# Adafruit_PowerBoost_1000_Basic.net
KiCad netlist of a schematic drawn in EAGLE
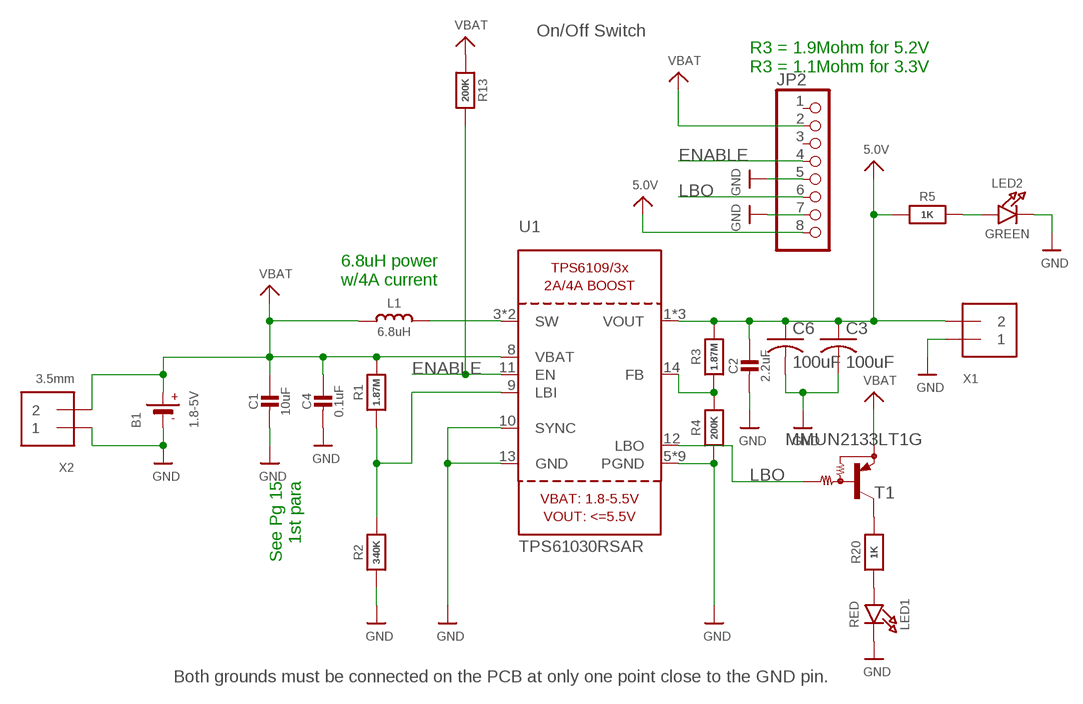
[diagram p0: schematic, sheet 1]

(export (version "E")
  (design (tool "Eeschema 10.0.6"))
  (components
    (comp (ref "B1")
      (value "1.8-5V")
      (footprint "eagle-import:JSTPH2")
      (libsource (lib "eagle-import") (part "BATTERY"))
    )
    (comp (ref "C1")
      (value "10uF")
      (footprint "eagle-import:0805-NO")
      (libsource (lib "eagle-import") (part "CAP_CERAMIC0805-NOOUTLINE"))
    )
    (comp (ref "C2")
      (value "2.2uF")
      (footprint "eagle-import:0805-NO")
      (libsource (lib "eagle-import") (part "CAP_CERAMIC0805-NOOUTLINE"))
    )
    (comp (ref "C3")
      (value "100uF")
      (footprint "eagle-import:C1210")
      (libsource (lib "eagle-import") (part "C-USC1210"))
    )
    (comp (ref "C4")
      (value "0.1uF")
      (footprint "eagle-import:0805-NO")
      (libsource (lib "eagle-import") (part "CAP_CERAMIC0805-NOOUTLINE"))
    )
    (comp (ref "C6")
      (value "100uF")
      (footprint "eagle-import:C1210")
      (libsource (lib "eagle-import") (part "C-USC1210"))
    )
    (comp (ref "JP2")
      (value "HEADER-1X8ROUND")
      (footprint "eagle-import:1X08_ROUND")
      (libsource (lib "eagle-import") (part "HEADER-1X8ROUND"))
    )
    (comp (ref "L1")
      (value "6.8uH")
      (footprint "eagle-import:INDUCTOR_8X8MM")
      (libsource (lib "eagle-import") (part "INDUCTOR-8X8"))
    )
    (comp (ref "LED1")
      (value "RED")
      (footprint "eagle-import:CHIPLED_0805_NOOUTLINE")
      (libsource (lib "eagle-import") (part "LED0805_NOOUTLINE"))
    )
    (comp (ref "LED2")
      (value "GREEN")
      (footprint "eagle-import:CHIPLED_0805_NOOUTLINE")
      (libsource (lib "eagle-import") (part "LED0805_NOOUTLINE"))
    )
    (comp (ref "R1")
      (value "1.87M")
      (footprint "eagle-import:_0805MP")
      (libsource (lib "eagle-import") (part "RESISTOR_0805MP"))
    )
    (comp (ref "R2")
      (value "340K")
      (footprint "eagle-import:_0805MP")
      (libsource (lib "eagle-import") (part "RESISTOR_0805MP"))
    )
    (comp (ref "R3")
      (value "1.87M")
      (footprint "eagle-import:_0805MP")
      (libsource (lib "eagle-import") (part "RESISTOR_0805MP"))
    )
    (comp (ref "R4")
      (value "200K")
      (footprint "eagle-import:0805-NO")
      (libsource (lib "eagle-import") (part "RESISTOR0805_NOOUTLINE"))
    )
    (comp (ref "R5")
      (value "1K")
      (footprint "eagle-import:0805-NO")
      (libsource (lib "eagle-import") (part "RESISTOR0805_NOOUTLINE"))
    )
    (comp (ref "R13")
      (value "200K")
      (footprint "eagle-import:0805-NO")
      (libsource (lib "eagle-import") (part "RESISTOR0805_NOOUTLINE"))
    )
    (comp (ref "R20")
      (value "1K")
      (footprint "eagle-import:0805-NO")
      (libsource (lib "eagle-import") (part "RESISTOR0805_NOOUTLINE"))
    )
    (comp (ref "T1")
      (value "MMUN2133LT1G")
      (footprint "eagle-import:SC59-BEC")
      (libsource (lib "eagle-import") (part "-PNP_DRIVER-SC59-BECMUN2114T1"))
    )
    (comp (ref "U1")
      (value "TPS61030RSAR")
      (footprint "eagle-import:PVQFN-16")
      (libsource (lib "eagle-import") (part "VREG_TPS6103X"))
    )
    (comp (ref "X1")
      (value "TERMBLOCK_1X2")
      (footprint "eagle-import:TERMBLOCK_1X2-3.5MM")
      (libsource (lib "eagle-import") (part "TERMBLOCK_1X2"))
    )
    (comp (ref "X2")
      (value "3.5mm")
      (footprint "eagle-import:TERMBLOCK_1X2-3.5MM")
      (libsource (lib "eagle-import") (part "TERMBLOCK_1X2"))
    )
  )
  (nets
    (net (code "1") (name "/ENABLE") (class "Default")
      (node (ref "JP2") (pin "4") (pinfunction "4_4") (pintype "passive"))
      (node (ref "R13") (pin "2") (pinfunction "2_2") (pintype "passive"))
      (node (ref "U1") (pin "11") (pinfunction "EN_11") (pintype "input"))
    )
    (net (code "2") (name "/LBO") (class "Default")
      (node (ref "JP2") (pin "6") (pinfunction "6_6") (pintype "passive"))
      (node (ref "T1") (pin "B") (pinfunction "B_B") (pintype "passive"))
      (node (ref "U1") (pin "12") (pinfunction "LBO_12") (pintype "output"))
    )
    (net (code "3") (name "5.0V") (class "Default")
      (node (ref "C2") (pin "1") (pinfunction "1_1") (pintype "passive"))
      (node (ref "C3") (pin "1") (pinfunction "1_1") (pintype "passive"))
      (node (ref "C6") (pin "1") (pinfunction "1_1") (pintype "passive"))
      (node (ref "JP2") (pin "8") (pinfunction "8_8") (pintype "passive"))
      (node (ref "R3") (pin "2") (pinfunction "2_2") (pintype "passive"))
      (node (ref "R5") (pin "1") (pinfunction "1_1") (pintype "passive"))
      (node (ref "U1") (pin "1") (pinfunction "VOUT_1") (pintype "power_in"))
      (node (ref "U1") (pin "15") (pinfunction "VOUT_15") (pintype "power_in"))
      (node (ref "U1") (pin "16") (pinfunction "VOUT_16") (pintype "power_in"))
      (node (ref "X1") (pin "2") (pinfunction "2_2") (pintype "passive"))
    )
    (net (code "4") (name "GND") (class "Default")
      (node (ref "B1") (pin "1") (pinfunction "-_1") (pintype "passive"))
      (node (ref "C1") (pin "2") (pinfunction "2_2") (pintype "passive"))
      (node (ref "C2") (pin "2") (pinfunction "2_2") (pintype "passive"))
      (node (ref "C3") (pin "2") (pinfunction "2_2") (pintype "passive"))
      (node (ref "C4") (pin "2") (pinfunction "2_2") (pintype "passive"))
      (node (ref "C6") (pin "2") (pinfunction "2_2") (pintype "passive"))
      (node (ref "JP2") (pin "5") (pinfunction "5_5") (pintype "passive"))
      (node (ref "JP2") (pin "7") (pinfunction "7_7") (pintype "passive"))
      (node (ref "LED1") (pin "C") (pinfunction "C_C") (pintype "passive"))
      (node (ref "LED2") (pin "C") (pinfunction "C_C") (pintype "passive"))
      (node (ref "R2") (pin "1") (pinfunction "1_1") (pintype "passive"))
      (node (ref "R4") (pin "1") (pinfunction "1_1") (pintype "passive"))
      (node (ref "U1") (pin "10") (pinfunction "SYNC_10") (pintype "input"))
      (node (ref "U1") (pin "13") (pinfunction "GND_13") (pintype "power_in"))
      (node (ref "U1") (pin "5") (pinfunction "PGND_5") (pintype "power_in"))
      (node (ref "U1") (pin "6") (pinfunction "PGND_6") (pintype "power_in"))
      (node (ref "U1") (pin "7") (pinfunction "PGND_7") (pintype "power_in"))
      (node (ref "U1") (pin "P$18") (pinfunction "PGND_P$18") (pintype "power_in"))
      (node (ref "U1") (pin "P$19") (pinfunction "PGND_P$19") (pintype "power_in"))
      (node (ref "U1") (pin "P$20") (pinfunction "PGND_P$20") (pintype "power_in"))
      (node (ref "U1") (pin "P$21") (pinfunction "PGND_P$21") (pintype "power_in"))
      (node (ref "U1") (pin "P$22") (pinfunction "PGND_P$22") (pintype "power_in"))
      (node (ref "U1") (pin "THERMAL") (pinfunction "PGND_THERMAL") (pintype "power_in"))
      (node (ref "X1") (pin "1") (pinfunction "1_1") (pintype "passive"))
      (node (ref "X2") (pin "1") (pinfunction "1_1") (pintype "passive"))
    )
    (net (code "5") (name "Net-(L1-2)") (class "Default")
      (node (ref "L1") (pin "P$2") (pinfunction "2_P$2") (pintype "passive"))
      (node (ref "U1") (pin "3") (pinfunction "SW_3") (pintype "input"))
      (node (ref "U1") (pin "4") (pinfunction "SW_4") (pintype "input"))
    )
    (net (code "6") (name "Net-(LED1-PadA)") (class "Default")
      (node (ref "LED1") (pin "A") (pinfunction "A_A") (pintype "passive"))
      (node (ref "R20") (pin "1") (pinfunction "1_1") (pintype "passive"))
    )
    (net (code "7") (name "Net-(LED2-PadA)") (class "Default")
      (node (ref "LED2") (pin "A") (pinfunction "A_A") (pintype "passive"))
      (node (ref "R5") (pin "2") (pinfunction "2_2") (pintype "passive"))
    )
    (net (code "8") (name "Net-(R20-Pad2)") (class "Default")
      (node (ref "R20") (pin "2") (pinfunction "2_2") (pintype "passive"))
      (node (ref "T1") (pin "C") (pinfunction "C_C") (pintype "passive"))
    )
    (net (code "9") (name "Net-(U1-FB)") (class "Default")
      (node (ref "R3") (pin "1") (pinfunction "1_1") (pintype "passive"))
      (node (ref "R4") (pin "2") (pinfunction "2_2") (pintype "passive"))
      (node (ref "U1") (pin "14") (pinfunction "FB_14") (pintype "input"))
    )
    (net (code "10") (name "Net-(U1-LBI)") (class "Default")
      (node (ref "R1") (pin "1") (pinfunction "1_1") (pintype "passive"))
      (node (ref "R2") (pin "2") (pinfunction "2_2") (pintype "passive"))
      (node (ref "U1") (pin "9") (pinfunction "LBI_9") (pintype "input"))
    )
    (net (code "11") (name "VBAT") (class "Default")
      (node (ref "B1") (pin "2") (pinfunction "+_2") (pintype "passive"))
      (node (ref "C1") (pin "1") (pinfunction "1_1") (pintype "passive"))
      (node (ref "C4") (pin "1") (pinfunction "1_1") (pintype "passive"))
      (node (ref "JP2") (pin "2") (pinfunction "2_2") (pintype "passive"))
      (node (ref "L1") (pin "P$1") (pinfunction "1_P$1") (pintype "passive"))
      (node (ref "R1") (pin "2") (pinfunction "2_2") (pintype "passive"))
      (node (ref "R13") (pin "1") (pinfunction "1_1") (pintype "passive"))
      (node (ref "T1") (pin "E") (pinfunction "E_E") (pintype "passive"))
      (node (ref "U1") (pin "8") (pinfunction "VBAT_8") (pintype "input"))
      (node (ref "X2") (pin "2") (pinfunction "2_2") (pintype "passive"))
    )
    (net (code "12") (name "unconnected-(JP2-Pad1)") (class "Default")
      (node (ref "JP2") (pin "1") (pinfunction "1_1") (pintype "passive"))
    )
    (net (code "13") (name "unconnected-(JP2-Pad3)") (class "Default")
      (node (ref "JP2") (pin "3") (pinfunction "3_3") (pintype "passive"))
    )
  )
)
